# MS_Gauge.net
KiCad netlist of a schematic drawn in EAGLE
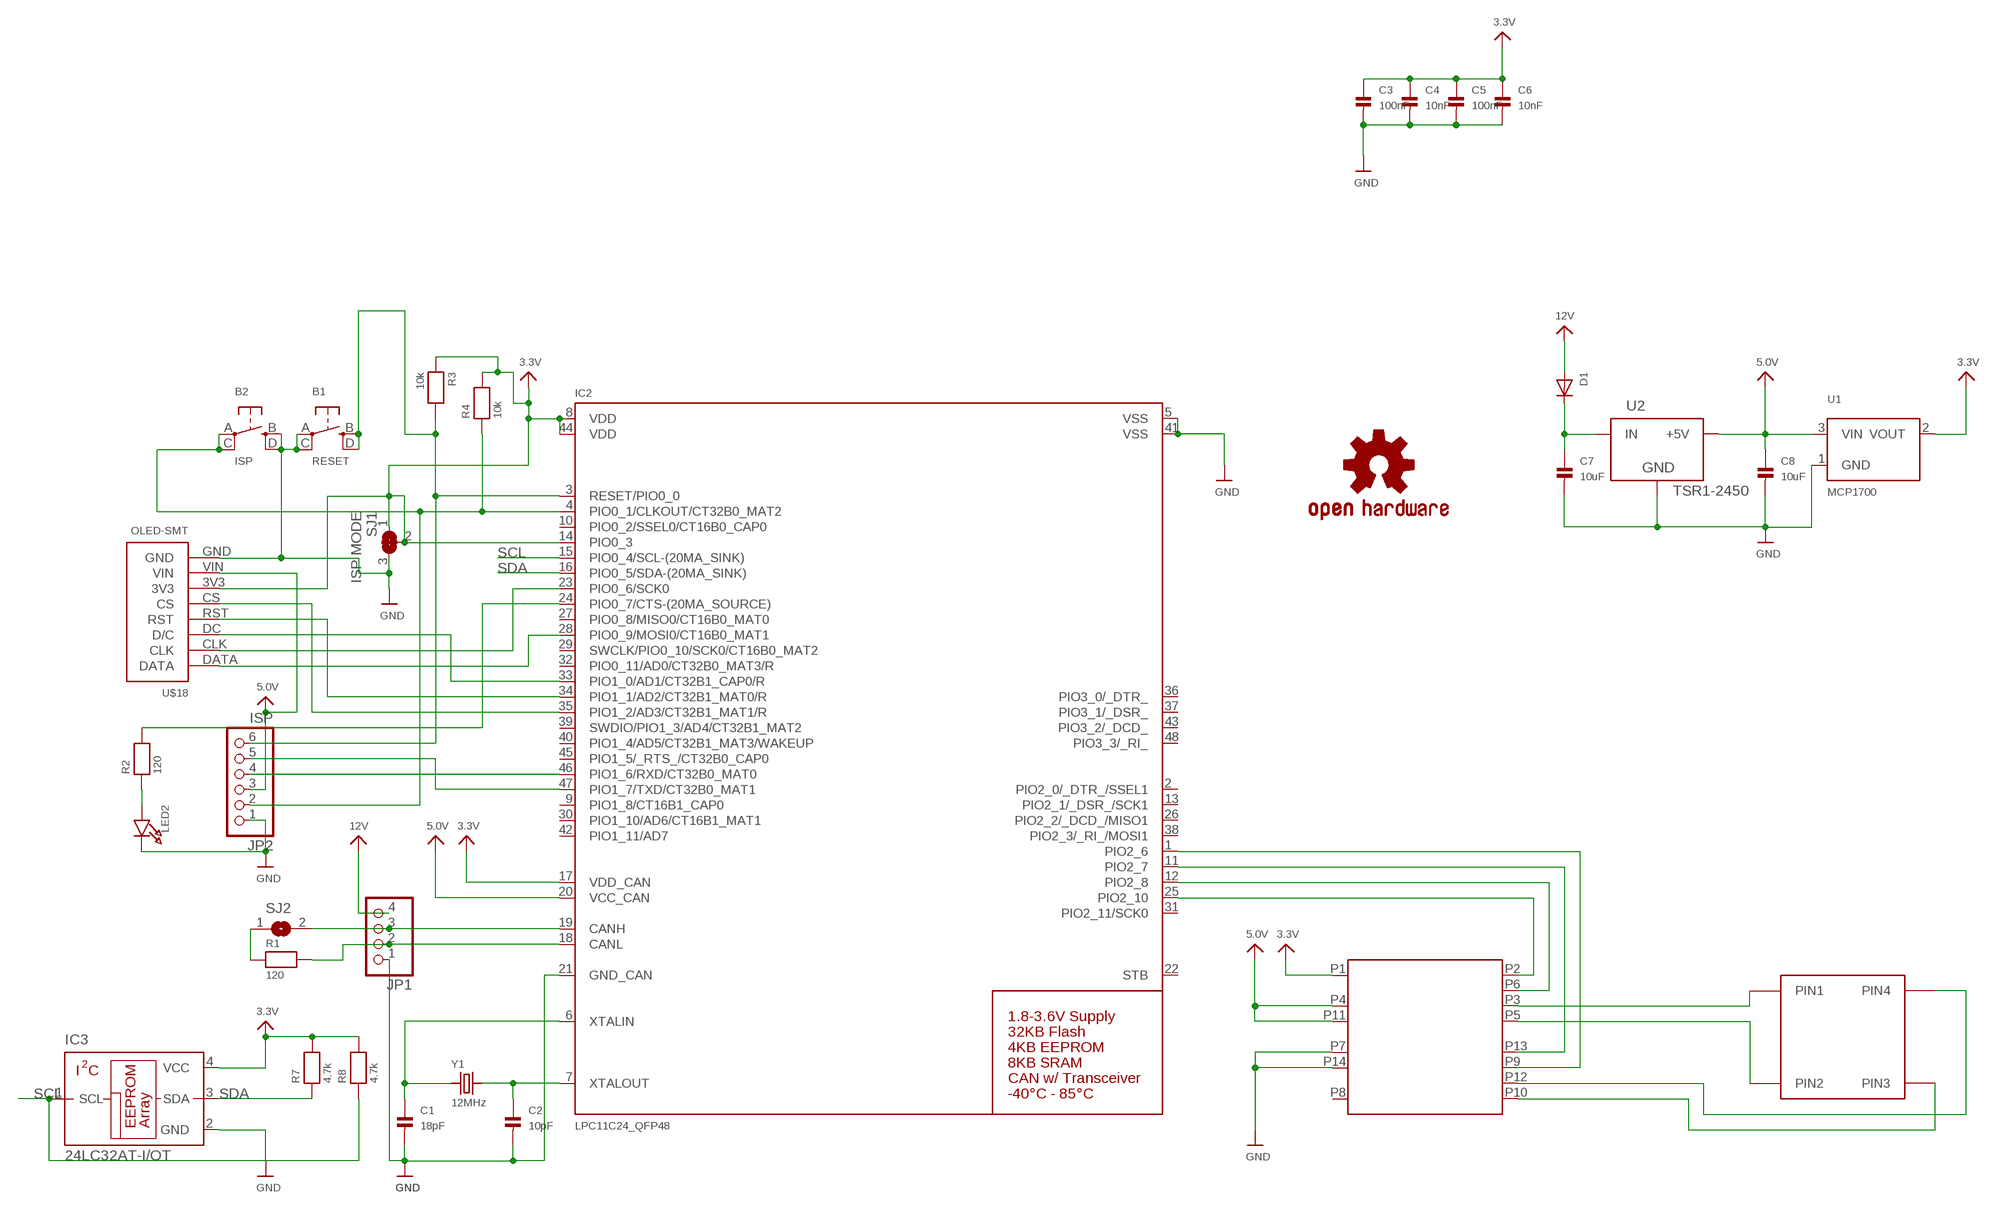
[diagram p0: schematic, sheet 1]

(export (version "E")
  (design (tool "Eeschema 10.0.6"))
  (components
    (comp (ref "B1")
      (value "RESET")
      (footprint "eagle-import:BTN_EVQPQ_4.5MM")
      (libsource (lib "eagle-import") (part "SWITCH_TACT_SMTEVQPQ"))
    )
    (comp (ref "B2")
      (value "ISP")
      (footprint "eagle-import:BTN_EVQPQ_4.5MM")
      (libsource (lib "eagle-import") (part "SWITCH_TACT_SMTEVQPQ"))
    )
    (comp (ref "C1")
      (value "18pF")
      (footprint "eagle-import:0603")
      (libsource (lib "eagle-import") (part "CAP_CERAMIC0603"))
    )
    (comp (ref "C2")
      (value "10pF")
      (footprint "eagle-import:0603")
      (libsource (lib "eagle-import") (part "CAP_CERAMIC0603"))
    )
    (comp (ref "C3")
      (value "100nF")
      (footprint "eagle-import:0603")
      (libsource (lib "eagle-import") (part "CAP_CERAMIC0603"))
    )
    (comp (ref "C4")
      (value "10nF")
      (footprint "eagle-import:0603")
      (libsource (lib "eagle-import") (part "CAP_CERAMIC0603"))
    )
    (comp (ref "C5")
      (value "100nF")
      (footprint "eagle-import:0603")
      (libsource (lib "eagle-import") (part "CAP_CERAMIC0603"))
    )
    (comp (ref "C6")
      (value "10nF")
      (footprint "eagle-import:0603")
      (libsource (lib "eagle-import") (part "CAP_CERAMIC0603"))
    )
    (comp (ref "C7")
      (value "10uF")
      (footprint "eagle-import:1206")
      (libsource (lib "eagle-import") (part "CAP_CERAMIC1206"))
    )
    (comp (ref "C8")
      (value "10uF")
      (footprint "eagle-import:1206")
      (libsource (lib "eagle-import") (part "CAP_CERAMIC1206"))
    )
    (comp (ref "D1")
      (value "DIODESMA")
      (footprint "eagle-import:SMADIODE")
      (libsource (lib "eagle-import") (part "DIODESMA"))
    )
    (comp (ref "IC1")
      (value "B1836M")
      (footprint "eagle-import:MFP14S")
      (libsource (lib "eagle-import") (part "B1836M"))
    )
    (comp (ref "IC2")
      (value "LPC11C24_QFP48")
      (footprint "eagle-import:LQFP48")
      (libsource (lib "eagle-import") (part "LPC11C24_QFP48"))
    )
    (comp (ref "IC3")
      (value "24LC32AT-I/OT")
      (footprint "eagle-import:SOT23-5L")
      (libsource (lib "eagle-import") (part "24LC32AT-I/OT"))
    )
    (comp (ref "JP1")
      (value "HEADER-1X4ROUND")
      (footprint "eagle-import:1X04_ROUND")
      (libsource (lib "eagle-import") (part "HEADER-1X4ROUND"))
    )
    (comp (ref "JP2")
      (value "ISP")
      (footprint "eagle-import:1X06_SMT")
      (libsource (lib "eagle-import") (part "HEADER-1X6SMT"))
    )
    (comp (ref "LED2")
      (value "LED0603")
      (footprint "eagle-import:CHIPLED_0603")
      (libsource (lib "eagle-import") (part "LED0603"))
    )
    (comp (ref "LOGO1")
      (value "OSHW-LOGOL")
      (footprint "eagle-import:OSHW-LOGO-L")
      (libsource (lib "eagle-import") (part "OSHW-LOGOL"))
    )
    (comp (ref "R1")
      (value "120")
      (footprint "eagle-import:0603")
      (libsource (lib "eagle-import") (part "RESISTOR0603"))
    )
    (comp (ref "R2")
      (value "120")
      (footprint "eagle-import:0603")
      (libsource (lib "eagle-import") (part "RESISTOR0603"))
    )
    (comp (ref "R3")
      (value "10k")
      (footprint "eagle-import:0603")
      (libsource (lib "eagle-import") (part "RESISTOR0603"))
    )
    (comp (ref "R4")
      (value "10k")
      (footprint "eagle-import:0603")
      (libsource (lib "eagle-import") (part "RESISTOR0603"))
    )
    (comp (ref "R7")
      (value "4.7k")
      (footprint "eagle-import:0603")
      (libsource (lib "eagle-import") (part "RESISTOR0603"))
    )
    (comp (ref "R8")
      (value "4.7k")
      (footprint "eagle-import:0603")
      (libsource (lib "eagle-import") (part "RESISTOR0603"))
    )
    (comp (ref "SJ1")
      (value "ISP MODE")
      (footprint "eagle-import:SOLDERJUMPER_2WAY_OPEN_0805")
      (libsource (lib "eagle-import") (part "SOLDERJUMPER_2WAY0805"))
    )
    (comp (ref "SJ2")
      (value "SOLDERJUMPER")
      (footprint "eagle-import:SOLDERJUMPER_ARROW_NOPASTE")
      (libsource (lib "eagle-import") (part "SOLDERJUMPER"))
    )
    (comp (ref "U$1")
      (value "VID29-FLIPPED")
      (footprint "eagle-import:VID29-FLIPPED")
      (libsource (lib "eagle-import") (part "VID29-FLIPPED"))
    )
    (comp (ref "U$18")
      (value "OLED-SMT")
      (footprint "eagle-import:OLED-1.3-SMT")
      (libsource (lib "eagle-import") (part "OLED-SMT"))
    )
    (comp (ref "U1")
      (value "MCP1700")
      (footprint "eagle-import:SOT23-R")
      (libsource (lib "eagle-import") (part "MCP1700"))
    )
    (comp (ref "U2")
      (value "TSR1-2450")
      (footprint "eagle-import:TSR-1")
      (libsource (lib "eagle-import") (part "TSR1-2450"))
    )
    (comp (ref "Y1")
      (value "12MHz")
      (footprint "eagle-import:CRYSTAL_3.2X2.5")
      (libsource (lib "eagle-import") (part "CRYSTALTHIN"))
    )
  )
  (nets
    (net (code "1") (name "/SCL") (class "Default")
      (node (ref "IC2") (pin "15") (pinfunction "PIO0_4/SCL-(20MA_SINK)_15") (pintype "bidirectional"))
      (node (ref "IC3") (pin "1") (pinfunction "SCL_1") (pintype "input"))
      (node (ref "R8") (pin "1") (pinfunction "1_1") (pintype "passive"))
    )
    (net (code "2") (name "/SDA") (class "Default")
      (node (ref "IC2") (pin "16") (pinfunction "PIO0_5/SDA-(20MA_SINK)_16") (pintype "bidirectional"))
      (node (ref "IC3") (pin "3") (pinfunction "SDA_3") (pintype "bidirectional"))
      (node (ref "R7") (pin "1") (pinfunction "1_1") (pintype "passive"))
    )
    (net (code "3") (name "3.3V") (class "Default")
      (node (ref "C3") (pin "1") (pinfunction "P$1_1") (pintype "passive"))
      (node (ref "C4") (pin "1") (pinfunction "P$1_1") (pintype "passive"))
      (node (ref "C5") (pin "1") (pinfunction "P$1_1") (pintype "passive"))
      (node (ref "C6") (pin "1") (pinfunction "P$1_1") (pintype "passive"))
      (node (ref "IC1") (pin "P1") (pinfunction "VCC_P1") (pintype "power_in"))
      (node (ref "IC2") (pin "14") (pinfunction "PIO0_3_14") (pintype "bidirectional"))
      (node (ref "IC2") (pin "17") (pinfunction "VDD_CAN_17") (pintype "bidirectional"))
      (node (ref "IC2") (pin "44") (pinfunction "VDD_44") (pintype "bidirectional"))
      (node (ref "IC2") (pin "8") (pinfunction "VDD_8") (pintype "bidirectional"))
      (node (ref "IC3") (pin "4") (pinfunction "VCC_4") (pintype "power_in"))
      (node (ref "R3") (pin "1") (pinfunction "1_1") (pintype "passive"))
      (node (ref "R4") (pin "2") (pinfunction "2_2") (pintype "passive"))
      (node (ref "R7") (pin "2") (pinfunction "2_2") (pintype "passive"))
      (node (ref "R8") (pin "2") (pinfunction "2_2") (pintype "passive"))
      (node (ref "SJ1") (pin "1") (pinfunction "1_1") (pintype "passive"))
      (node (ref "SJ1") (pin "2") (pinfunction "2_2") (pintype "passive"))
      (node (ref "U$18") (pin "3V3") (pinfunction "3V3_3V3") (pintype "bidirectional"))
      (node (ref "U1") (pin "2") (pinfunction "VOUT_2") (pintype "power_in"))
    )
    (net (code "4") (name "5.0V") (class "Default")
      (node (ref "C8") (pin "1") (pinfunction "P$1_1") (pintype "passive"))
      (node (ref "IC1") (pin "P11") (pinfunction "VS2_P11") (pintype "bidirectional"))
      (node (ref "IC1") (pin "P4") (pinfunction "VS1_P4") (pintype "bidirectional"))
      (node (ref "IC2") (pin "20") (pinfunction "VCC_CAN_20") (pintype "bidirectional"))
      (node (ref "JP2") (pin "3") (pinfunction "3_3") (pintype "passive"))
      (node (ref "U$18") (pin "VIN") (pinfunction "VIN_VIN") (pintype "bidirectional"))
      (node (ref "U1") (pin "3") (pinfunction "VIN_3") (pintype "power_in"))
      (node (ref "U2") (pin "3") (pinfunction "+5V_3") (pintype "power_in"))
    )
    (net (code "5") (name "12V") (class "Default")
      (node (ref "D1") (pin "A") (pinfunction "A_A") (pintype "passive"))
      (node (ref "JP1") (pin "4") (pinfunction "4_4") (pintype "passive"))
    )
    (net (code "6") (name "GND") (class "Default")
      (node (ref "B1") (pin "A") (pinfunction "P_A") (pintype "passive"))
      (node (ref "B1") (pin "C") (pinfunction "P1_C") (pintype "passive"))
      (node (ref "B2") (pin "B") (pinfunction "S_B") (pintype "passive"))
      (node (ref "B2") (pin "D") (pinfunction "S1_D") (pintype "passive"))
      (node (ref "C1") (pin "2") (pinfunction "P$2_2") (pintype "passive"))
      (node (ref "C2") (pin "2") (pinfunction "P$2_2") (pintype "passive"))
      (node (ref "C3") (pin "2") (pinfunction "P$2_2") (pintype "passive"))
      (node (ref "C4") (pin "2") (pinfunction "P$2_2") (pintype "passive"))
      (node (ref "C5") (pin "2") (pinfunction "P$2_2") (pintype "passive"))
      (node (ref "C6") (pin "2") (pinfunction "P$2_2") (pintype "passive"))
      (node (ref "C7") (pin "2") (pinfunction "P$2_2") (pintype "passive"))
      (node (ref "C8") (pin "2") (pinfunction "P$2_2") (pintype "passive"))
      (node (ref "IC1") (pin "P14") (pinfunction "GND2_P14") (pintype "power_in"))
      (node (ref "IC1") (pin "P7") (pinfunction "GND1_P7") (pintype "power_in"))
      (node (ref "IC2") (pin "21") (pinfunction "GND_CAN_21") (pintype "bidirectional"))
      (node (ref "IC2") (pin "41") (pinfunction "VSS_41") (pintype "bidirectional"))
      (node (ref "IC2") (pin "5") (pinfunction "VSS_5") (pintype "bidirectional"))
      (node (ref "IC3") (pin "2") (pinfunction "GND_2") (pintype "power_in"))
      (node (ref "JP1") (pin "1") (pinfunction "1_1") (pintype "passive"))
      (node (ref "JP2") (pin "1") (pinfunction "1_1") (pintype "passive"))
      (node (ref "LED2") (pin "C") (pinfunction "C_C") (pintype "passive"))
      (node (ref "SJ1") (pin "3") (pinfunction "3_3") (pintype "passive"))
      (node (ref "U$18") (pin "GND") (pinfunction "GND_GND") (pintype "bidirectional"))
      (node (ref "U1") (pin "1") (pinfunction "GND_1") (pintype "power_in"))
      (node (ref "U2") (pin "2") (pinfunction "GND_2") (pintype "power_in"))
    )
    (net (code "7") (name "Net-(B1-S)") (class "Default")
      (node (ref "B1") (pin "B") (pinfunction "S_B") (pintype "passive"))
      (node (ref "B1") (pin "D") (pinfunction "S1_D") (pintype "passive"))
      (node (ref "IC2") (pin "3") (pinfunction "RESET/PIO0_0_3") (pintype "bidirectional"))
      (node (ref "JP2") (pin "6") (pinfunction "6_6") (pintype "passive"))
      (node (ref "R3") (pin "2") (pinfunction "2_2") (pintype "passive"))
    )
    (net (code "8") (name "Net-(B2-P)") (class "Default")
      (node (ref "B2") (pin "A") (pinfunction "P_A") (pintype "passive"))
      (node (ref "B2") (pin "C") (pinfunction "P1_C") (pintype "passive"))
      (node (ref "IC2") (pin "4") (pinfunction "PIO0_1/CLKOUT/CT32B0_MAT2_4") (pintype "bidirectional"))
      (node (ref "JP2") (pin "2") (pinfunction "2_2") (pintype "passive"))
      (node (ref "R4") (pin "1") (pinfunction "1_1") (pintype "passive"))
    )
    (net (code "9") (name "Net-(C1-P$1)") (class "Default")
      (node (ref "C1") (pin "1") (pinfunction "P$1_1") (pintype "passive"))
      (node (ref "IC2") (pin "6") (pinfunction "XTALIN_6") (pintype "bidirectional"))
      (node (ref "Y1") (pin "1") (pinfunction "1_1") (pintype "passive"))
    )
    (net (code "10") (name "Net-(C2-P$1)") (class "Default")
      (node (ref "C2") (pin "1") (pinfunction "P$1_1") (pintype "passive"))
      (node (ref "IC2") (pin "7") (pinfunction "XTALOUT_7") (pintype "bidirectional"))
      (node (ref "Y1") (pin "2") (pinfunction "2_2") (pintype "passive"))
    )
    (net (code "11") (name "Net-(C7-P$1)") (class "Default")
      (node (ref "C7") (pin "1") (pinfunction "P$1_1") (pintype "passive"))
      (node (ref "D1") (pin "C") (pinfunction "C_C") (pintype "passive"))
      (node (ref "U2") (pin "1") (pinfunction "IN_1") (pintype "power_in"))
    )
    (net (code "12") (name "Net-(IC1-IN1)") (class "Default")
      (node (ref "IC1") (pin "P2") (pinfunction "IN1_P2") (pintype "input"))
      (node (ref "IC2") (pin "25") (pinfunction "PIO2_10_25") (pintype "bidirectional"))
    )
    (net (code "13") (name "Net-(IC1-IN2)") (class "Default")
      (node (ref "IC1") (pin "P6") (pinfunction "IN2_P6") (pintype "input"))
      (node (ref "IC2") (pin "12") (pinfunction "PIO2_8_12") (pintype "bidirectional"))
    )
    (net (code "14") (name "Net-(IC1-IN3)") (class "Default")
      (node (ref "IC1") (pin "P13") (pinfunction "IN3_P13") (pintype "input"))
      (node (ref "IC2") (pin "11") (pinfunction "PIO2_7_11") (pintype "bidirectional"))
    )
    (net (code "15") (name "Net-(IC1-IN4)") (class "Default")
      (node (ref "IC1") (pin "P9") (pinfunction "IN4_P9") (pintype "input"))
      (node (ref "IC2") (pin "1") (pinfunction "PIO2_6_1") (pintype "bidirectional"))
    )
    (net (code "16") (name "Net-(IC1-OUT1)") (class "Default")
      (node (ref "IC1") (pin "P3") (pinfunction "OUT1_P3") (pintype "output"))
      (node (ref "U$1") (pin "PIN1") (pinfunction "PIN1_PIN1") (pintype "bidirectional"))
    )
    (net (code "17") (name "Net-(IC1-OUT2)") (class "Default")
      (node (ref "IC1") (pin "P5") (pinfunction "OUT2_P5") (pintype "output"))
      (node (ref "U$1") (pin "PIN2") (pinfunction "PIN2_PIN2") (pintype "bidirectional"))
    )
    (net (code "18") (name "Net-(IC1-OUT3)") (class "Default")
      (node (ref "IC1") (pin "P12") (pinfunction "OUT3_P12") (pintype "output"))
      (node (ref "U$1") (pin "PIN4") (pinfunction "PIN4_PIN4") (pintype "bidirectional"))
    )
    (net (code "19") (name "Net-(IC1-OUT4)") (class "Default")
      (node (ref "IC1") (pin "P10") (pinfunction "OUT4_P10") (pintype "output"))
      (node (ref "U$1") (pin "PIN3") (pinfunction "PIN3_PIN3") (pintype "bidirectional"))
    )
    (net (code "20") (name "Net-(IC2-CANH)") (class "Default")
      (node (ref "IC2") (pin "19") (pinfunction "CANH_19") (pintype "bidirectional"))
      (node (ref "JP1") (pin "3") (pinfunction "3_3") (pintype "passive"))
      (node (ref "SJ2") (pin "2") (pinfunction "2_2") (pintype "passive"))
    )
    (net (code "21") (name "Net-(IC2-CANL)") (class "Default")
      (node (ref "IC2") (pin "18") (pinfunction "CANL_18") (pintype "bidirectional"))
      (node (ref "JP1") (pin "2") (pinfunction "2_2") (pintype "passive"))
      (node (ref "R1") (pin "2") (pinfunction "2_2") (pintype "passive"))
    )
    (net (code "22") (name "Net-(IC2-PIO0_6{slash}SCK0)") (class "Default")
      (node (ref "IC2") (pin "23") (pinfunction "PIO0_6/SCK0_23") (pintype "bidirectional"))
      (node (ref "U$18") (pin "CLK") (pinfunction "CLK_CLK") (pintype "bidirectional"))
    )
    (net (code "23") (name "Net-(IC2-PIO0_7{slash}CTS-(20MA_SOURCE))") (class "Default")
      (node (ref "IC2") (pin "24") (pinfunction "PIO0_7/CTS-(20MA_SOURCE)_24") (pintype "bidirectional"))
      (node (ref "R2") (pin "2") (pinfunction "2_2") (pintype "passive"))
    )
    (net (code "24") (name "Net-(IC2-PIO0_9{slash}MOSI0{slash}CT16B0_MAT1)") (class "Default")
      (node (ref "IC2") (pin "28") (pinfunction "PIO0_9/MOSI0/CT16B0_MAT1_28") (pintype "bidirectional"))
      (node (ref "U$18") (pin "DATA") (pinfunction "DATA_DATA") (pintype "bidirectional"))
    )
    (net (code "25") (name "Net-(IC2-PIO1_0{slash}AD1{slash}CT32B1_CAP0{slash}R)") (class "Default")
      (node (ref "IC2") (pin "33") (pinfunction "PIO1_0/AD1/CT32B1_CAP0/R_33") (pintype "bidirectional"))
      (node (ref "U$18") (pin "DC") (pinfunction "D/C_DC") (pintype "bidirectional"))
    )
    (net (code "26") (name "Net-(IC2-PIO1_1{slash}AD2{slash}CT32B1_MAT0{slash}R)") (class "Default")
      (node (ref "IC2") (pin "34") (pinfunction "PIO1_1/AD2/CT32B1_MAT0/R_34") (pintype "bidirectional"))
      (node (ref "U$18") (pin "RST") (pinfunction "RST_RST") (pintype "bidirectional"))
    )
    (net (code "27") (name "Net-(IC2-PIO1_2{slash}AD3{slash}CT32B1_MAT1{slash}R)") (class "Default")
      (node (ref "IC2") (pin "35") (pinfunction "PIO1_2/AD3/CT32B1_MAT1/R_35") (pintype "bidirectional"))
      (node (ref "U$18") (pin "CS") (pinfunction "CS_CS") (pintype "bidirectional"))
    )
    (net (code "28") (name "Net-(IC2-PIO1_6{slash}RXD{slash}CT32B0_MAT0)") (class "Default")
      (node (ref "IC2") (pin "46") (pinfunction "PIO1_6/RXD/CT32B0_MAT0_46") (pintype "bidirectional"))
      (node (ref "JP2") (pin "4") (pinfunction "4_4") (pintype "passive"))
    )
    (net (code "29") (name "Net-(IC2-PIO1_7{slash}TXD{slash}CT32B0_MAT1)") (class "Default")
      (node (ref "IC2") (pin "47") (pinfunction "PIO1_7/TXD/CT32B0_MAT1_47") (pintype "bidirectional"))
      (node (ref "JP2") (pin "5") (pinfunction "5_5") (pintype "passive"))
    )
    (net (code "30") (name "Net-(LED2-PadA)") (class "Default")
      (node (ref "LED2") (pin "A") (pinfunction "A_A") (pintype "passive"))
      (node (ref "R2") (pin "1") (pinfunction "1_1") (pintype "passive"))
    )
    (net (code "31") (name "Net-(R1-Pad1)") (class "Default")
      (node (ref "R1") (pin "1") (pinfunction "1_1") (pintype "passive"))
      (node (ref "SJ2") (pin "1") (pinfunction "1_1") (pintype "passive"))
    )
    (net (code "32") (name "unconnected-(IC1-VCONT-PadP8)") (class "Default")
      (node (ref "IC1") (pin "P8") (pinfunction "VCONT_P8") (pintype "bidirectional"))
    )
    (net (code "33") (name "unconnected-(IC2-PIO0_2{slash}SSEL0{slash}CT16B0_CAP0-Pad10)") (class "Default")
      (node (ref "IC2") (pin "10") (pinfunction "PIO0_2/SSEL0/CT16B0_CAP0_10") (pintype "bidirectional"))
    )
    (net (code "34") (name "unconnected-(IC2-PIO0_8{slash}MISO0{slash}CT16B0_MAT0-Pad27)") (class "Default")
      (node (ref "IC2") (pin "27") (pinfunction "PIO0_8/MISO0/CT16B0_MAT0_27") (pintype "bidirectional"))
    )
    (net (code "35") (name "unconnected-(IC2-PIO0_11{slash}AD0{slash}CT32B0_MAT3{slash}R-Pad32)") (class "Default")
      (node (ref "IC2") (pin "32") (pinfunction "PIO0_11/AD0/CT32B0_MAT3/R_32") (pintype "bidirectional"))
    )
    (net (code "36") (name "unconnected-(IC2-PIO1_4{slash}AD5{slash}CT32B1_MAT3{slash}WAKEUP-Pad40)") (class "Default")
      (node (ref "IC2") (pin "40") (pinfunction "PIO1_4/AD5/CT32B1_MAT3/WAKEUP_40") (pintype "bidirectional"))
    )
    (net (code "37") (name "unconnected-(IC2-PIO1_5{slash}_RTS_{slash}CT32B0_CAP0-Pad45)") (class "Default")
      (node (ref "IC2") (pin "45") (pinfunction "PIO1_5/_RTS_/CT32B0_CAP0_45") (pintype "bidirectional"))
    )
    (net (code "38") (name "unconnected-(IC2-PIO1_8{slash}CT16B1_CAP0-Pad9)") (class "Default")
      (node (ref "IC2") (pin "9") (pinfunction "PIO1_8/CT16B1_CAP0_9") (pintype "bidirectional"))
    )
    (net (code "39") (name "unconnected-(IC2-PIO1_10{slash}AD6{slash}CT16B1_MAT1-Pad30)") (class "Default")
      (node (ref "IC2") (pin "30") (pinfunction "PIO1_10/AD6/CT16B1_MAT1_30") (pintype "bidirectional"))
    )
    (net (code "40") (name "unconnected-(IC2-PIO1_11{slash}AD7-Pad42)") (class "Default")
      (node (ref "IC2") (pin "42") (pinfunction "PIO1_11/AD7_42") (pintype "bidirectional"))
    )
    (net (code "41") (name "unconnected-(IC2-PIO2_0{slash}_DTR_{slash}SSEL1-Pad2)") (class "Default")
      (node (ref "IC2") (pin "2") (pinfunction "PIO2_0/_DTR_/SSEL1_2") (pintype "bidirectional"))
    )
    (net (code "42") (name "unconnected-(IC2-PIO2_1{slash}_DSR_{slash}SCK1-Pad13)") (class "Default")
      (node (ref "IC2") (pin "13") (pinfunction "PIO2_1/_DSR_/SCK1_13") (pintype "bidirectional"))
    )
    (net (code "43") (name "unconnected-(IC2-PIO2_2{slash}_DCD_{slash}MISO1-Pad26)") (class "Default")
      (node (ref "IC2") (pin "26") (pinfunction "PIO2_2/_DCD_/MISO1_26") (pintype "bidirectional"))
    )
    (net (code "44") (name "unconnected-(IC2-PIO2_3{slash}_RI_{slash}MOSI1-Pad38)") (class "Default")
      (node (ref "IC2") (pin "38") (pinfunction "PIO2_3/_RI_/MOSI1_38") (pintype "bidirectional"))
    )
    (net (code "45") (name "unconnected-(IC2-PIO2_11{slash}SCK0-Pad31)") (class "Default")
      (node (ref "IC2") (pin "31") (pinfunction "PIO2_11/SCK0_31") (pintype "bidirectional"))
    )
    (net (code "46") (name "unconnected-(IC2-PIO3_0{slash}_DTR_-Pad36)") (class "Default")
      (node (ref "IC2") (pin "36") (pinfunction "PIO3_0/_DTR__36") (pintype "bidirectional"))
    )
    (net (code "47") (name "unconnected-(IC2-PIO3_1{slash}_DSR_-Pad37)") (class "Default")
      (node (ref "IC2") (pin "37") (pinfunction "PIO3_1/_DSR__37") (pintype "bidirectional"))
    )
    (net (code "48") (name "unconnected-(IC2-PIO3_2{slash}_DCD_-Pad43)") (class "Default")
      (node (ref "IC2") (pin "43") (pinfunction "PIO3_2/_DCD__43") (pintype "bidirectional"))
    )
    (net (code "49") (name "unconnected-(IC2-PIO3_3{slash}_RI_-Pad48)") (class "Default")
      (node (ref "IC2") (pin "48") (pinfunction "PIO3_3/_RI__48") (pintype "bidirectional"))
    )
    (net (code "50") (name "unconnected-(IC2-STB-Pad22)") (class "Default")
      (node (ref "IC2") (pin "22") (pinfunction "STB_22") (pintype "bidirectional"))
    )
    (net (code "51") (name "unconnected-(IC2-SWCLK{slash}PIO0_10{slash}SCK0{slash}CT16B0_MAT2-Pad29)") (class "Default")
      (node (ref "IC2") (pin "29") (pinfunction "SWCLK/PIO0_10/SCK0/CT16B0_MAT2_29") (pintype "bidirectional"))
    )
    (net (code "52") (name "unconnected-(IC2-SWDIO{slash}PIO1_3{slash}AD4{slash}CT32B1_MAT2-Pad39)") (class "Default")
      (node (ref "IC2") (pin "39") (pinfunction "SWDIO/PIO1_3/AD4/CT32B1_MAT2_39") (pintype "bidirectional"))
    )
  )
)
